# BUTTONS_LEDS.net
KiCad netlist of a schematic drawn in Altium Designer
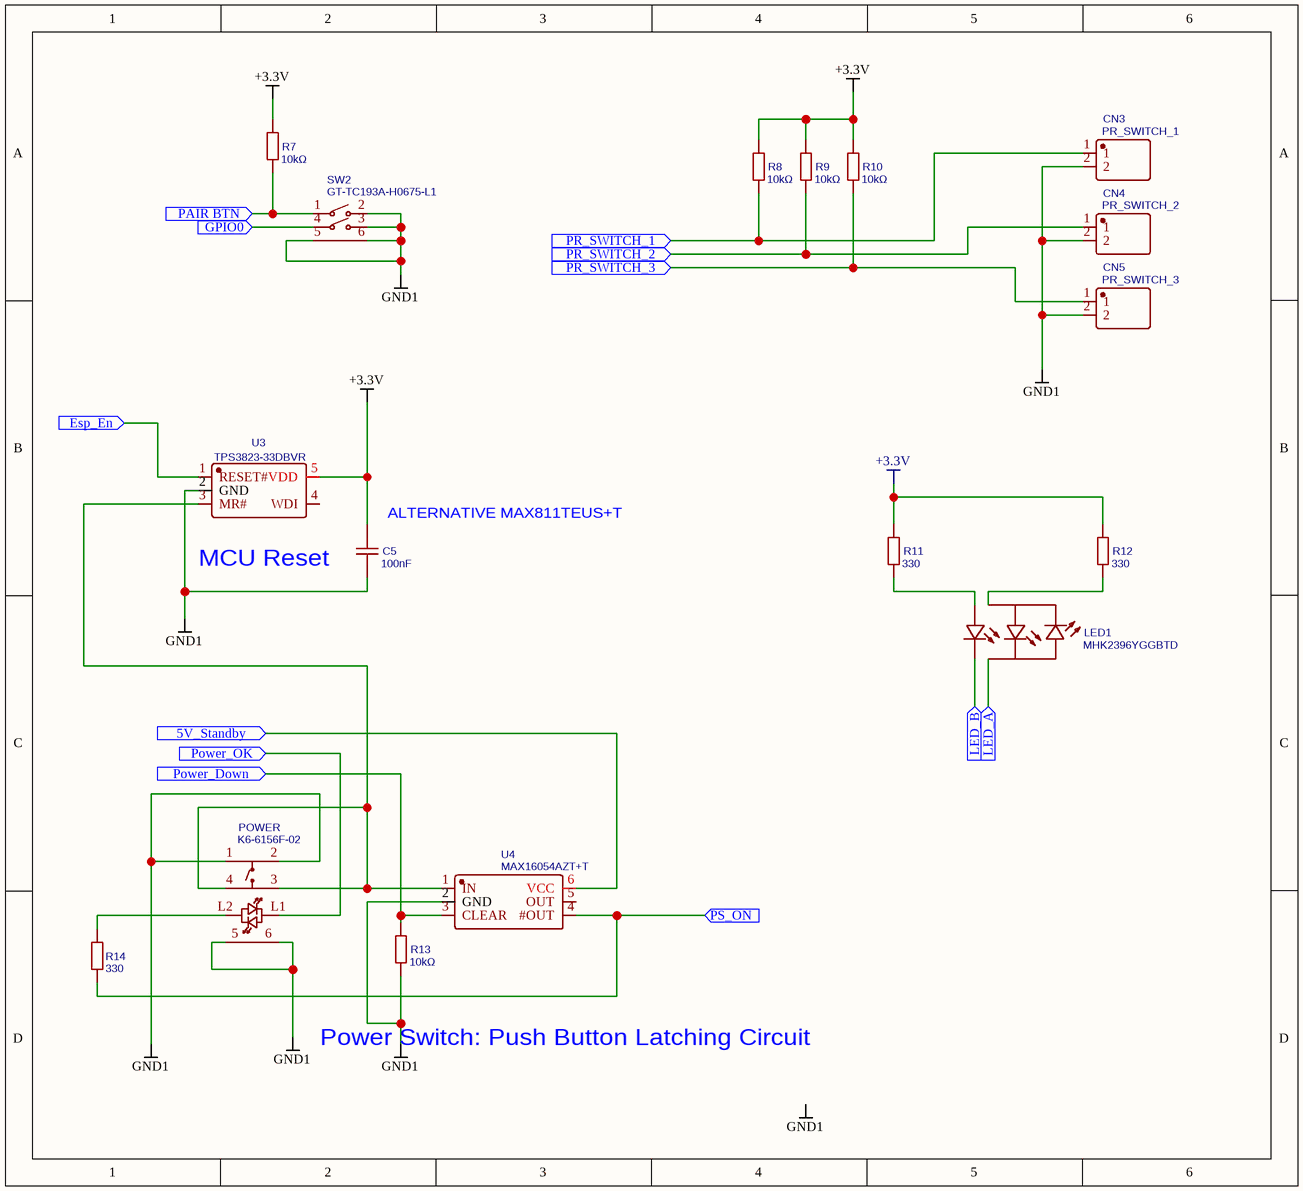
[diagram p0: BUTTONS_LEDS.schdoc]

(export (version "E")
  (design (tool "Eeschema 10.0.6"))
  (components
    (comp (ref "C5")
      (value "100nF")
      (fields
        (field (name "BOM_SUPPLIER PART") "C519981")
        (field (name "BOM_MANUFACTURER PART") "CC0805KRX7R8BB104")
        (field (name "CONTRIBUTOR") "LCSC")
      )
      (libsource (lib "altium-import") (part "root_1_100nF_"))
    )
    (comp (ref "CN3")
      (value "PR_SWITCH_1")
      (fields (field (name "BOM_SUPPLIER PART") "C161869") (field (name "CONTRIBUTOR") "LCSC"))
      (libsource (lib "altium-import") (part "root_0_PR_SWITCH_1_"))
    )
    (comp (ref "CN4")
      (value "PR_SWITCH_2")
      (fields (field (name "BOM_SUPPLIER PART") "C161869") (field (name "CONTRIBUTOR") "LCSC"))
      (libsource (lib "altium-import") (part "root_0_PR_SWITCH_2_"))
    )
    (comp (ref "CN5")
      (value "PR_SWITCH_3")
      (fields (field (name "BOM_SUPPLIER PART") "C161869") (field (name "CONTRIBUTOR") "LCSC"))
      (libsource (lib "altium-import") (part "root_0_PR_SWITCH_3_"))
    )
    (comp (ref "LED1")
      (value "MHK2396YGGBTD")
      (fields (field (name "BOM_SUPPLIER PART") "C409768") (field (name "CONTRIBUTOR") "LCSC"))
      (libsource (lib "altium-import") (part "root_3_MHK2396YGGBTD_"))
    )
    (comp (ref "POWER")
      (value "K6-6156F-02")
      (fields (field (name "BOM_SUPPLIER PART") "C2848638") (field (name "CONTRIBUTOR") "LCSC"))
      (libsource (lib "altium-import") (part "root_0_K6-6156F-02_"))
    )
    (comp (ref "R7")
      (value "10kΩ")
      (fields
        (field (name "BOM_SUPPLIER PART") "C332266")
        (field (name "BOM_MANUFACTURER PART") "TR0805D10KP0550")
        (field (name "CONTRIBUTOR") "LCSC")
      )
      (libsource (lib "altium-import") (part "root_1_10kΩ_"))
    )
    (comp (ref "R8")
      (value "10kΩ")
      (fields
        (field (name "BOM_SUPPLIER PART") "C332266")
        (field (name "BOM_MANUFACTURER PART") "TR0805D10KP0550")
        (field (name "CONTRIBUTOR") "LCSC")
      )
      (libsource (lib "altium-import") (part "root_1_10kΩ_"))
    )
    (comp (ref "R9")
      (value "10kΩ")
      (fields
        (field (name "BOM_SUPPLIER PART") "C332266")
        (field (name "BOM_MANUFACTURER PART") "TR0805D10KP0550")
        (field (name "CONTRIBUTOR") "LCSC")
      )
      (libsource (lib "altium-import") (part "root_1_10kΩ_"))
    )
    (comp (ref "R10")
      (value "10kΩ")
      (fields
        (field (name "BOM_SUPPLIER PART") "C332266")
        (field (name "BOM_MANUFACTURER PART") "TR0805D10KP0550")
        (field (name "CONTRIBUTOR") "LCSC")
      )
      (libsource (lib "altium-import") (part "root_1_10kΩ_"))
    )
    (comp (ref "R11")
      (value "330")
      (fields
        (field (name "BOM_MANUFACTURER PART") "AC0805FR-07330RL")
        (field (name "BOM_SUPPLIER PART") "C144564")
        (field (name "CONTRIBUTOR") "LCSC")
      )
      (libsource (lib "altium-import") (part "root_1_330_"))
    )
    (comp (ref "R12")
      (value "330")
      (fields
        (field (name "BOM_MANUFACTURER PART") "AC0805FR-07330RL")
        (field (name "BOM_SUPPLIER PART") "C144564")
        (field (name "CONTRIBUTOR") "LCSC")
      )
      (libsource (lib "altium-import") (part "root_1_330_"))
    )
    (comp (ref "R13")
      (value "10kΩ")
      (fields
        (field (name "BOM_SUPPLIER PART") "C332266")
        (field (name "BOM_MANUFACTURER PART") "TR0805D10KP0550")
        (field (name "CONTRIBUTOR") "LCSC")
      )
      (libsource (lib "altium-import") (part "root_1_10kΩ_"))
    )
    (comp (ref "R14")
      (value "330")
      (fields
        (field (name "BOM_MANUFACTURER PART") "AC0805FR-07330RL")
        (field (name "BOM_SUPPLIER PART") "C144564")
        (field (name "CONTRIBUTOR") "LCSC")
      )
      (libsource (lib "altium-import") (part "root_1_330_"))
    )
    (comp (ref "SW2")
      (value "GT-TC193A-H0675-L1")
      (fields (field (name "BOM_SUPPLIER PART") "C2835017") (field (name "CONTRIBUTOR") "LCSC"))
      (libsource (lib "altium-import") (part "root_0_GT-TC193A-H0675-L1_"))
    )
    (comp (ref "U3")
      (value "TPS3823-33DBVR")
      (fields (field (name "BOM_SUPPLIER PART") "C7719"))
      (libsource (lib "altium-import") (part "root_0_TPS3823-33DBVR_"))
    )
    (comp (ref "U4")
      (value "MAX16054AZT+T")
      (fields (field (name "BOM_SUPPLIER PART") "C79401") (field (name "CONTRIBUTOR") "LCSC"))
      (libsource (lib "altium-import") (part "root_0_MAX16054AZT+T_"))
    )
  )
  (nets
    (net (code "1") (name "+3.3V") (class "Default")
      (node (ref "C5") (pin "2") (pinfunction "2_2") (pintype "passive"))
      (node (ref "R10") (pin "2") (pinfunction "2_2") (pintype "passive"))
      (node (ref "R11") (pin "2") (pinfunction "2_2") (pintype "passive"))
      (node (ref "R12") (pin "2") (pinfunction "2_2") (pintype "passive"))
      (node (ref "R7") (pin "2") (pinfunction "2_2") (pintype "passive"))
      (node (ref "R8") (pin "2") (pinfunction "2_2") (pintype "passive"))
      (node (ref "R9") (pin "2") (pinfunction "2_2") (pintype "passive"))
      (node (ref "U3") (pin "5") (pinfunction "VDD_5") (pintype "passive"))
    )
    (net (code "2") (name "/5V_Standby") (class "Default")
      (node (ref "U4") (pin "6") (pinfunction "VCC_6") (pintype "passive"))
    )
    (net (code "3") (name "/Esp_En") (class "Default")
      (node (ref "U3") (pin "1") (pinfunction "RESET#_1") (pintype "passive"))
    )
    (net (code "4") (name "/GPIO0") (class "Default")
      (node (ref "SW2") (pin "4") (pinfunction "c_4") (pintype "passive"))
    )
    (net (code "5") (name "/LED_A") (class "Default")
      (node (ref "LED1") (pin "2") (pinfunction "2_2") (pintype "passive"))
    )
    (net (code "6") (name "/LED_B") (class "Default")
      (node (ref "LED1") (pin "4") (pinfunction "4_4") (pintype "passive"))
    )
    (net (code "7") (name "/PAIR BTN") (class "Default")
      (node (ref "R7") (pin "1") (pinfunction "1_1") (pintype "passive"))
      (node (ref "SW2") (pin "1") (pinfunction "a_1") (pintype "passive"))
    )
    (net (code "8") (name "/PR_SWITCH_1") (class "Default")
      (node (ref "CN3") (pin "1") (pinfunction "1_1") (pintype "passive"))
      (node (ref "R8") (pin "1") (pinfunction "1_1") (pintype "passive"))
    )
    (net (code "9") (name "/PR_SWITCH_2") (class "Default")
      (node (ref "CN4") (pin "1") (pinfunction "1_1") (pintype "passive"))
      (node (ref "R9") (pin "1") (pinfunction "1_1") (pintype "passive"))
    )
    (net (code "10") (name "/PR_SWITCH_3") (class "Default")
      (node (ref "CN5") (pin "1") (pinfunction "1_1") (pintype "passive"))
      (node (ref "R10") (pin "1") (pinfunction "1_1") (pintype "passive"))
    )
    (net (code "11") (name "/PS_ON") (class "Default")
      (node (ref "R14") (pin "1") (pinfunction "1_1") (pintype "passive"))
      (node (ref "U4") (pin "4") (pinfunction "#OUT_4") (pintype "passive"))
    )
    (net (code "12") (name "/Power_Down") (class "Default")
      (node (ref "R13") (pin "2") (pinfunction "2_2") (pintype "passive"))
      (node (ref "U4") (pin "3") (pinfunction "CLEAR_3") (pintype "passive"))
    )
    (net (code "13") (name "/Power_OK") (class "Default")
      (node (ref "POWER") (pin "L1") (pinfunction "L1_L1") (pintype "passive"))
    )
    (net (code "14") (name "GND1") (class "Default")
      (node (ref "C5") (pin "1") (pinfunction "1_1") (pintype "passive"))
      (node (ref "CN3") (pin "2") (pinfunction "2_2") (pintype "passive"))
      (node (ref "CN4") (pin "2") (pinfunction "2_2") (pintype "passive"))
      (node (ref "CN5") (pin "2") (pinfunction "2_2") (pintype "passive"))
      (node (ref "POWER") (pin "1") (pinfunction "1_1") (pintype "passive"))
      (node (ref "POWER") (pin "2") (pinfunction "2_2") (pintype "passive"))
      (node (ref "POWER") (pin "5") (pinfunction "5_5") (pintype "passive"))
      (node (ref "POWER") (pin "6") (pinfunction "6_6") (pintype "passive"))
      (node (ref "R13") (pin "1") (pinfunction "1_1") (pintype "passive"))
      (node (ref "SW2") (pin "2") (pinfunction "b_2") (pintype "passive"))
      (node (ref "SW2") (pin "3") (pinfunction "d_3") (pintype "passive"))
      (node (ref "SW2") (pin "5") (pinfunction "5_5") (pintype "passive"))
      (node (ref "SW2") (pin "6") (pinfunction "6_6") (pintype "passive"))
      (node (ref "U3") (pin "2") (pinfunction "GND_2") (pintype "passive"))
      (node (ref "U4") (pin "2") (pinfunction "GND_2") (pintype "passive"))
    )
    (net (code "15") (name "Net-(LED1-Pad1)") (class "Default")
      (node (ref "LED1") (pin "1") (pinfunction "1_1") (pintype "passive"))
      (node (ref "R12") (pin "1") (pinfunction "1_1") (pintype "passive"))
    )
    (net (code "16") (name "Net-(LED1-Pad3)") (class "Default")
      (node (ref "LED1") (pin "3") (pinfunction "3_3") (pintype "passive"))
      (node (ref "R11") (pin "1") (pinfunction "1_1") (pintype "passive"))
    )
    (net (code "17") (name "Net-(POWER-PadL2)") (class "Default")
      (node (ref "POWER") (pin "L2") (pinfunction "L2_L2") (pintype "passive"))
      (node (ref "R14") (pin "2") (pinfunction "2_2") (pintype "passive"))
    )
    (net (code "18") (name "Net-(U3-MR#)") (class "Default")
      (node (ref "POWER") (pin "3") (pinfunction "3_3") (pintype "passive"))
      (node (ref "POWER") (pin "4") (pinfunction "4_4") (pintype "passive"))
      (node (ref "U3") (pin "3") (pinfunction "MR#_3") (pintype "passive"))
      (node (ref "U4") (pin "1") (pinfunction "IN_1") (pintype "passive"))
    )
    (net (code "19") (name "unconnected-(U3-WDI-Pad4)") (class "Default")
      (node (ref "U3") (pin "4") (pinfunction "WDI_4") (pintype "passive"))
    )
    (net (code "20") (name "unconnected-(U4-OUT-Pad5)") (class "Default")
      (node (ref "U4") (pin "5") (pinfunction "OUT_5") (pintype "passive"))
    )
  )
)
